# TouchPanel_ver__4.net
KiCad netlist of a schematic drawn in EAGLE
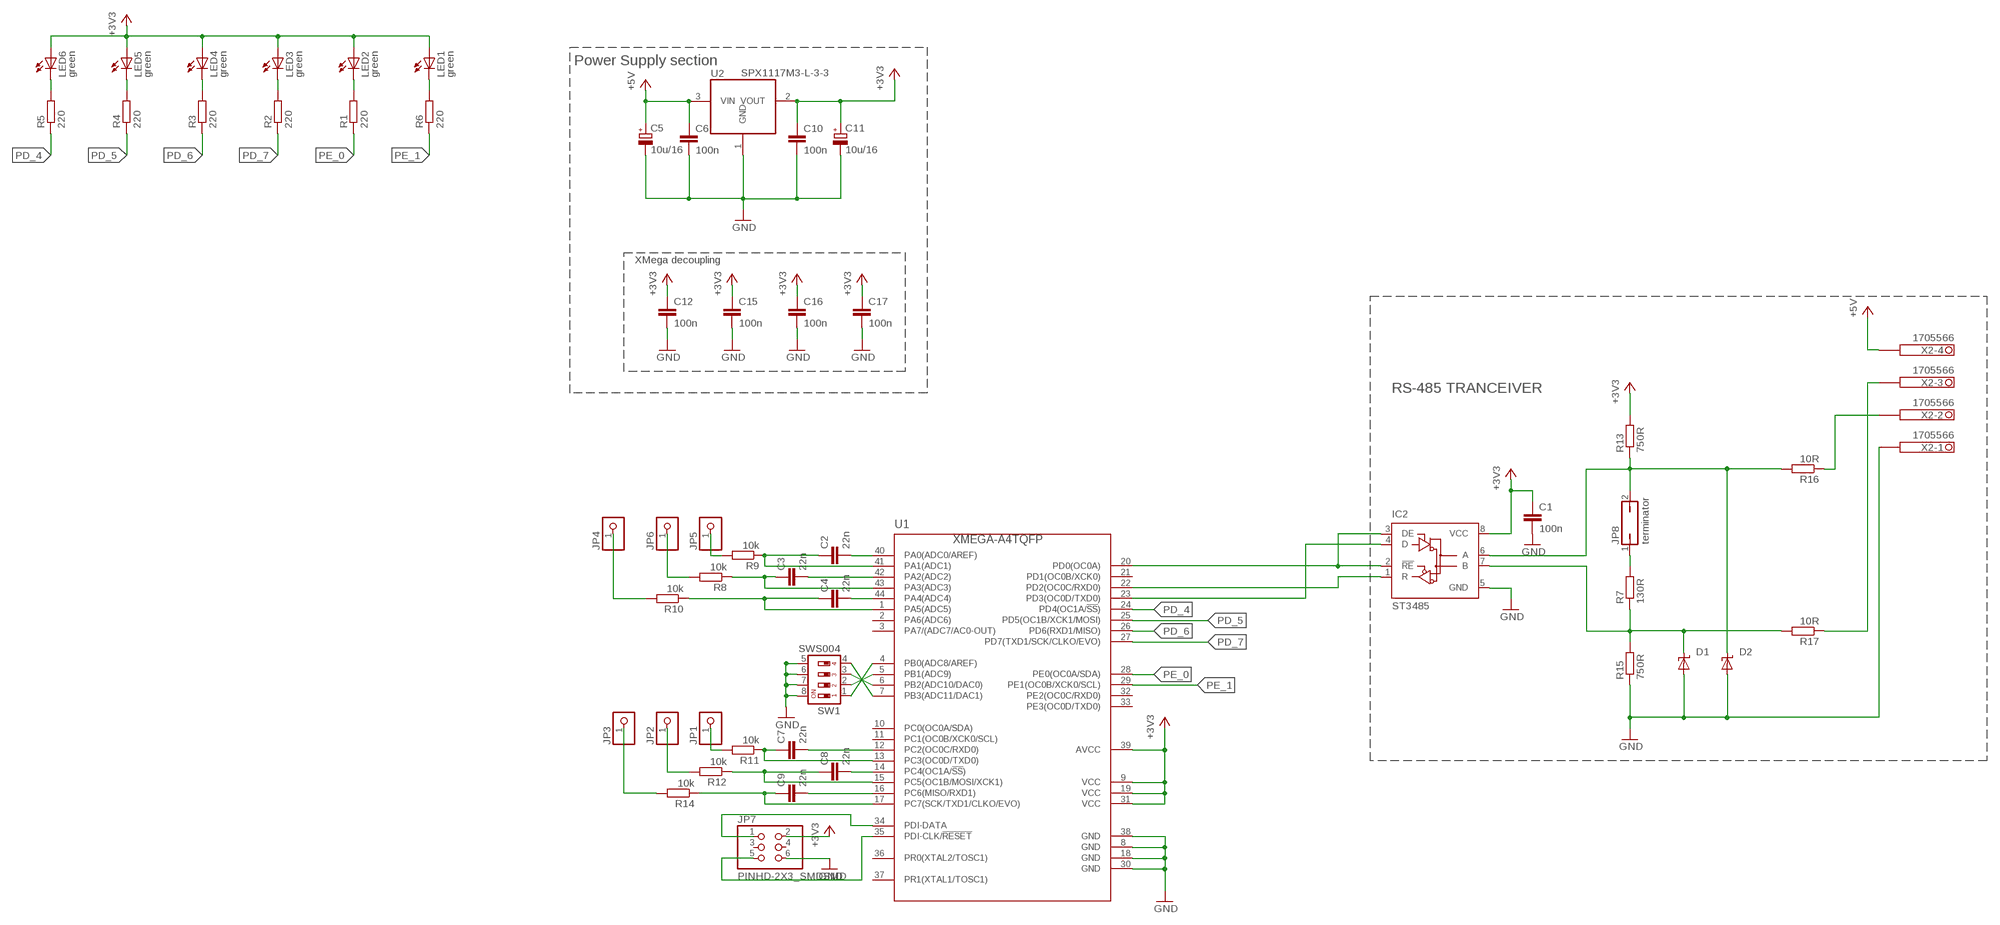
[diagram p0: schematic, sheet 1]

(export (version "E")
  (design (tool "Eeschema 10.0.6"))
  (components
    (comp (ref "C1")
      (value "100n")
      (footprint "eagle-import:C1206")
      (libsource (lib "eagle-import") (part "C-EUC1206"))
    )
    (comp (ref "C2")
      (value "22n")
      (footprint "eagle-import:C1206")
      (libsource (lib "eagle-import") (part "C-EUC1206"))
    )
    (comp (ref "C3")
      (value "22n")
      (footprint "eagle-import:C1206")
      (libsource (lib "eagle-import") (part "C-EUC1206"))
    )
    (comp (ref "C4")
      (value "22n")
      (footprint "eagle-import:C1206")
      (libsource (lib "eagle-import") (part "C-EUC1206"))
    )
    (comp (ref "C5")
      (value "10u/16")
      (footprint "eagle-import:SMC_B")
      (libsource (lib "eagle-import") (part "CPOL-EUSMCB"))
    )
    (comp (ref "C6")
      (value "100n")
      (footprint "eagle-import:C1206")
      (libsource (lib "eagle-import") (part "C-EUC1206"))
    )
    (comp (ref "C7")
      (value "22n")
      (footprint "eagle-import:C1206")
      (libsource (lib "eagle-import") (part "C-EUC1206"))
    )
    (comp (ref "C8")
      (value "22n")
      (footprint "eagle-import:C1206")
      (libsource (lib "eagle-import") (part "C-EUC1206"))
    )
    (comp (ref "C9")
      (value "22n")
      (footprint "eagle-import:C1206")
      (libsource (lib "eagle-import") (part "C-EUC1206"))
    )
    (comp (ref "C10")
      (value "100n")
      (footprint "eagle-import:C1206")
      (libsource (lib "eagle-import") (part "C-EUC1206"))
    )
    (comp (ref "C11")
      (value "10u/16")
      (footprint "eagle-import:SMC_B")
      (libsource (lib "eagle-import") (part "CPOL-EUSMCB"))
    )
    (comp (ref "C12")
      (value "100n")
      (footprint "eagle-import:C1206")
      (libsource (lib "eagle-import") (part "C-EUC1206"))
    )
    (comp (ref "C15")
      (value "100n")
      (footprint "eagle-import:C1206")
      (libsource (lib "eagle-import") (part "C-EUC1206"))
    )
    (comp (ref "C16")
      (value "100n")
      (footprint "eagle-import:C1206")
      (libsource (lib "eagle-import") (part "C-EUC1206"))
    )
    (comp (ref "C17")
      (value "100n")
      (footprint "eagle-import:C1206")
      (libsource (lib "eagle-import") (part "C-EUC1206"))
    )
    (comp (ref "D1")
      (value "SUPPRESSOR-SMBJ")
      (footprint "eagle-import:SMBJ")
      (libsource (lib "eagle-import") (part "SUPPRESSOR-SMBJ"))
    )
    (comp (ref "D2")
      (value "SUPPRESSOR-SMBJ")
      (footprint "eagle-import:SMBJ")
      (libsource (lib "eagle-import") (part "SUPPRESSOR-SMBJ"))
    )
    (comp (ref "IC2")
      (value "ST3485")
      (footprint "eagle-import:D_R-PDSO-G8")
      (libsource (lib "eagle-import") (part "75176AD"))
    )
    (comp (ref "JP1")
      (value "PINHD-1X1")
      (footprint "eagle-import:1X01")
      (libsource (lib "eagle-import") (part "PINHD-1X1"))
    )
    (comp (ref "JP2")
      (value "PINHD-1X1")
      (footprint "eagle-import:1X01")
      (libsource (lib "eagle-import") (part "PINHD-1X1"))
    )
    (comp (ref "JP3")
      (value "PINHD-1X1")
      (footprint "eagle-import:1X01")
      (libsource (lib "eagle-import") (part "PINHD-1X1"))
    )
    (comp (ref "JP4")
      (value "PINHD-1X1")
      (footprint "eagle-import:1X01")
      (libsource (lib "eagle-import") (part "PINHD-1X1"))
    )
    (comp (ref "JP5")
      (value "PINHD-1X1")
      (footprint "eagle-import:1X01")
      (libsource (lib "eagle-import") (part "PINHD-1X1"))
    )
    (comp (ref "JP6")
      (value "PINHD-1X1")
      (footprint "eagle-import:1X01")
      (libsource (lib "eagle-import") (part "PINHD-1X1"))
    )
    (comp (ref "JP7")
      (value "PINHD-2X3_SMDSMD")
      (footprint "eagle-import:2X03_SMD")
      (libsource (lib "eagle-import") (part "PINHD-2X3_SMDSMD"))
    )
    (comp (ref "JP8")
      (value "terminator")
      (footprint "eagle-import:JP1")
      (libsource (lib "eagle-import") (part "JP1Q"))
    )
    (comp (ref "LED1")
      (value "green")
      (footprint "eagle-import:MINI-TOPLED-SANTANA")
      (libsource (lib "eagle-import") (part "LEDTOPLED-SANTANA"))
    )
    (comp (ref "LED2")
      (value "green")
      (footprint "eagle-import:MINI-TOPLED-SANTANA")
      (libsource (lib "eagle-import") (part "LEDTOPLED-SANTANA"))
    )
    (comp (ref "LED3")
      (value "green")
      (footprint "eagle-import:MINI-TOPLED-SANTANA")
      (libsource (lib "eagle-import") (part "LEDTOPLED-SANTANA"))
    )
    (comp (ref "LED4")
      (value "green")
      (footprint "eagle-import:MINI-TOPLED-SANTANA")
      (libsource (lib "eagle-import") (part "LEDTOPLED-SANTANA"))
    )
    (comp (ref "LED5")
      (value "green")
      (footprint "eagle-import:MINI-TOPLED-SANTANA")
      (libsource (lib "eagle-import") (part "LEDTOPLED-SANTANA"))
    )
    (comp (ref "LED6")
      (value "green")
      (footprint "eagle-import:MINI-TOPLED-SANTANA")
      (libsource (lib "eagle-import") (part "LEDTOPLED-SANTANA"))
    )
    (comp (ref "R1")
      (value "220")
      (footprint "eagle-import:M1206")
      (libsource (lib "eagle-import") (part "R-EU_M1206"))
    )
    (comp (ref "R2")
      (value "220")
      (footprint "eagle-import:M1206")
      (libsource (lib "eagle-import") (part "R-EU_M1206"))
    )
    (comp (ref "R3")
      (value "220")
      (footprint "eagle-import:R1206")
      (libsource (lib "eagle-import") (part "R-EU_R1206"))
    )
    (comp (ref "R4")
      (value "220")
      (footprint "eagle-import:R1206")
      (libsource (lib "eagle-import") (part "R-EU_R1206"))
    )
    (comp (ref "R5")
      (value "220")
      (footprint "eagle-import:R1206")
      (libsource (lib "eagle-import") (part "R-EU_R1206"))
    )
    (comp (ref "R6")
      (value "220")
      (footprint "eagle-import:M1206")
      (libsource (lib "eagle-import") (part "R-EU_M1206"))
    )
    (comp (ref "R7")
      (value "130R")
      (footprint "eagle-import:M1206")
      (libsource (lib "eagle-import") (part "R-EU_M1206"))
    )
    (comp (ref "R8")
      (value "10k")
      (footprint "eagle-import:R1206")
      (libsource (lib "eagle-import") (part "R-EU_R1206"))
    )
    (comp (ref "R9")
      (value "10k")
      (footprint "eagle-import:R1206")
      (libsource (lib "eagle-import") (part "R-EU_R1206"))
    )
    (comp (ref "R10")
      (value "10k")
      (footprint "eagle-import:R1206")
      (libsource (lib "eagle-import") (part "R-EU_R1206"))
    )
    (comp (ref "R11")
      (value "10k")
      (footprint "eagle-import:R1206")
      (libsource (lib "eagle-import") (part "R-EU_R1206"))
    )
    (comp (ref "R12")
      (value "10k")
      (footprint "eagle-import:R1206")
      (libsource (lib "eagle-import") (part "R-EU_R1206"))
    )
    (comp (ref "R13")
      (value "750R")
      (footprint "eagle-import:M1206")
      (libsource (lib "eagle-import") (part "R-EU_M1206"))
    )
    (comp (ref "R14")
      (value "10k")
      (footprint "eagle-import:R1206")
      (libsource (lib "eagle-import") (part "R-EU_R1206"))
    )
    (comp (ref "R15")
      (value "750R")
      (footprint "eagle-import:M1206")
      (libsource (lib "eagle-import") (part "R-EU_M1206"))
    )
    (comp (ref "R16")
      (value "10R")
      (footprint "eagle-import:M1206")
      (libsource (lib "eagle-import") (part "R-EU_M1206"))
    )
    (comp (ref "R17")
      (value "10R")
      (footprint "eagle-import:M1206")
      (libsource (lib "eagle-import") (part "R-EU_M1206"))
    )
    (comp (ref "SW1")
      (value "SWS004")
      (footprint "eagle-import:SMS-004")
      (libsource (lib "eagle-import") (part "SWS004"))
    )
    (comp (ref "U1")
      (value "XMEGA-A4TQFP")
      (footprint "eagle-import:TQFP44")
      (libsource (lib "eagle-import") (part "XMEGA-A4TQFP"))
    )
    (comp (ref "U2")
      (value "SPX1117M3-L-3-3")
      (footprint "eagle-import:SOT223")
      (fields (field (name "MPN") "REG1117"))
      (libsource (lib "eagle-import") (part "REG1117"))
    )
    (comp (ref "X2")
      (value "1705566")
      (footprint "eagle-import:1705566")
      (libsource (lib "eagle-import") (part "1705566"))
    )
  )
  (nets
    (net (code "1") (name "+3V3") (class "Default")
      (node (ref "C1") (pin "1") (pinfunction "1_1") (pintype "passive"))
      (node (ref "C10") (pin "1") (pinfunction "1_1") (pintype "passive"))
      (node (ref "C11") (pin "+") (pinfunction "+_+") (pintype "passive"))
      (node (ref "C12") (pin "1") (pinfunction "1_1") (pintype "passive"))
      (node (ref "C15") (pin "1") (pinfunction "1_1") (pintype "passive"))
      (node (ref "C16") (pin "1") (pinfunction "1_1") (pintype "passive"))
      (node (ref "C17") (pin "1") (pinfunction "1_1") (pintype "passive"))
      (node (ref "IC2") (pin "8") (pinfunction "VCC_8") (pintype "power_in"))
      (node (ref "JP7") (pin "2") (pinfunction "2_2") (pintype "passive"))
      (node (ref "LED1") (pin "A") (pinfunction "A_A") (pintype "passive"))
      (node (ref "LED2") (pin "A") (pinfunction "A_A") (pintype "passive"))
      (node (ref "LED3") (pin "A") (pinfunction "A_A") (pintype "passive"))
      (node (ref "LED4") (pin "A") (pinfunction "A_A") (pintype "passive"))
      (node (ref "LED5") (pin "A") (pinfunction "A_A") (pintype "passive"))
      (node (ref "LED6") (pin "A") (pinfunction "A_A") (pintype "passive"))
      (node (ref "R13") (pin "2") (pinfunction "2_2") (pintype "passive"))
      (node (ref "U1") (pin "19") (pinfunction "VCC_19") (pintype "power_in"))
      (node (ref "U1") (pin "31") (pinfunction "VCC_31") (pintype "power_in"))
      (node (ref "U1") (pin "39") (pinfunction "AVCC_39") (pintype "power_in"))
      (node (ref "U1") (pin "9") (pinfunction "VCC_9") (pintype "power_in"))
      (node (ref "U2") (pin "2") (pinfunction "VOUT_2") (pintype "output"))
    )
    (net (code "2") (name "+5V") (class "Default")
      (node (ref "C5") (pin "+") (pinfunction "+_+") (pintype "passive"))
      (node (ref "C6") (pin "1") (pinfunction "1_1") (pintype "passive"))
      (node (ref "U2") (pin "3") (pinfunction "VIN_3") (pintype "input"))
      (node (ref "X2") (pin "4.2") (pinfunction "1B_4.2") (pintype "passive"))
    )
    (net (code "3") (name "GND") (class "Default")
      (node (ref "C1") (pin "2") (pinfunction "2_2") (pintype "passive"))
      (node (ref "C10") (pin "2") (pinfunction "2_2") (pintype "passive"))
      (node (ref "C11") (pin "-") (pinfunction "-_-") (pintype "passive"))
      (node (ref "C12") (pin "2") (pinfunction "2_2") (pintype "passive"))
      (node (ref "C15") (pin "2") (pinfunction "2_2") (pintype "passive"))
      (node (ref "C16") (pin "2") (pinfunction "2_2") (pintype "passive"))
      (node (ref "C17") (pin "2") (pinfunction "2_2") (pintype "passive"))
      (node (ref "C5") (pin "-") (pinfunction "-_-") (pintype "passive"))
      (node (ref "C6") (pin "2") (pinfunction "2_2") (pintype "passive"))
      (node (ref "D1") (pin "A") (pinfunction "A_A") (pintype "passive"))
      (node (ref "D2") (pin "A") (pinfunction "A_A") (pintype "passive"))
      (node (ref "IC2") (pin "5") (pinfunction "GND_5") (pintype "power_in"))
      (node (ref "JP7") (pin "6") (pinfunction "6_6") (pintype "passive"))
      (node (ref "R15") (pin "1") (pinfunction "1_1") (pintype "passive"))
      (node (ref "SW1") (pin "5") (pinfunction "5_5") (pintype "passive"))
      (node (ref "SW1") (pin "6") (pinfunction "6_6") (pintype "passive"))
      (node (ref "SW1") (pin "7") (pinfunction "7_7") (pintype "passive"))
      (node (ref "SW1") (pin "8") (pinfunction "8_8") (pintype "passive"))
      (node (ref "U1") (pin "18") (pinfunction "GND_18") (pintype "power_in"))
      (node (ref "U1") (pin "30") (pinfunction "GND_30") (pintype "power_in"))
      (node (ref "U1") (pin "38") (pinfunction "GND_38") (pintype "power_in"))
      (node (ref "U1") (pin "8") (pinfunction "GND_8") (pintype "power_in"))
      (node (ref "U2") (pin "1") (pinfunction "GND_1") (pintype "power_in"))
      (node (ref "X2") (pin "1.2") (pinfunction "1B_1.2") (pintype "passive"))
    )
    (net (code "4") (name "Net-(IC2-A)") (class "Default")
      (node (ref "D2") (pin "C") (pinfunction "C_C") (pintype "passive"))
      (node (ref "IC2") (pin "6") (pinfunction "A_6") (pintype "output"))
      (node (ref "JP8") (pin "2") (pinfunction "2_2") (pintype "passive"))
      (node (ref "R13") (pin "1") (pinfunction "1_1") (pintype "passive"))
      (node (ref "R16") (pin "2") (pinfunction "2_2") (pintype "passive"))
    )
    (net (code "5") (name "Net-(IC2-B)") (class "Default")
      (node (ref "D1") (pin "C") (pinfunction "C_C") (pintype "passive"))
      (node (ref "IC2") (pin "7") (pinfunction "B_7") (pintype "output"))
      (node (ref "R15") (pin "2") (pinfunction "2_2") (pintype "passive"))
      (node (ref "R17") (pin "2") (pinfunction "2_2") (pintype "passive"))
      (node (ref "R7") (pin "1") (pinfunction "1_1") (pintype "passive"))
    )
    (net (code "6") (name "Net-(IC2-D)") (class "Default")
      (node (ref "IC2") (pin "4") (pinfunction "D_4") (pintype "input"))
      (node (ref "U1") (pin "23") (pinfunction "PD3(OC0D/TXD0)_23") (pintype "bidirectional"))
    )
    (net (code "7") (name "Net-(IC2-DE)") (class "Default")
      (node (ref "IC2") (pin "2") (pinfunction "~{RE}_2") (pintype "input"))
      (node (ref "IC2") (pin "3") (pinfunction "DE_3") (pintype "input"))
      (node (ref "U1") (pin "20") (pinfunction "PD0(OC0A)_20") (pintype "bidirectional"))
    )
    (net (code "8") (name "Net-(IC2-R)") (class "Default")
      (node (ref "IC2") (pin "1") (pinfunction "R_1") (pintype "input"))
      (node (ref "U1") (pin "22") (pinfunction "PD2(OC0C/RXD0)_22") (pintype "bidirectional"))
    )
    (net (code "9") (name "Net-(JP1-Pad1)") (class "Default")
      (node (ref "JP1") (pin "1") (pinfunction "1_1") (pintype "passive"))
      (node (ref "R11") (pin "2") (pinfunction "2_2") (pintype "passive"))
    )
    (net (code "10") (name "Net-(JP2-Pad1)") (class "Default")
      (node (ref "JP2") (pin "1") (pinfunction "1_1") (pintype "passive"))
      (node (ref "R12") (pin "2") (pinfunction "2_2") (pintype "passive"))
    )
    (net (code "11") (name "Net-(JP3-Pad1)") (class "Default")
      (node (ref "JP3") (pin "1") (pinfunction "1_1") (pintype "passive"))
      (node (ref "R14") (pin "2") (pinfunction "2_2") (pintype "passive"))
    )
    (net (code "12") (name "Net-(JP4-Pad1)") (class "Default")
      (node (ref "JP4") (pin "1") (pinfunction "1_1") (pintype "passive"))
      (node (ref "R10") (pin "2") (pinfunction "2_2") (pintype "passive"))
    )
    (net (code "13") (name "Net-(JP5-Pad1)") (class "Default")
      (node (ref "JP5") (pin "1") (pinfunction "1_1") (pintype "passive"))
      (node (ref "R9") (pin "2") (pinfunction "2_2") (pintype "passive"))
    )
    (net (code "14") (name "Net-(JP6-Pad1)") (class "Default")
      (node (ref "JP6") (pin "1") (pinfunction "1_1") (pintype "passive"))
      (node (ref "R8") (pin "2") (pinfunction "2_2") (pintype "passive"))
    )
    (net (code "15") (name "Net-(JP8-Pad1)") (class "Default")
      (node (ref "JP8") (pin "1") (pinfunction "1_1") (pintype "passive"))
      (node (ref "R7") (pin "2") (pinfunction "2_2") (pintype "passive"))
    )
    (net (code "16") (name "Net-(LED1-PadC)") (class "Default")
      (node (ref "LED1") (pin "C") (pinfunction "C_C") (pintype "passive"))
      (node (ref "R6") (pin "2") (pinfunction "2_2") (pintype "passive"))
    )
    (net (code "17") (name "Net-(LED2-PadC)") (class "Default")
      (node (ref "LED2") (pin "C") (pinfunction "C_C") (pintype "passive"))
      (node (ref "R1") (pin "2") (pinfunction "2_2") (pintype "passive"))
    )
    (net (code "18") (name "Net-(LED3-PadC)") (class "Default")
      (node (ref "LED3") (pin "C") (pinfunction "C_C") (pintype "passive"))
      (node (ref "R2") (pin "2") (pinfunction "2_2") (pintype "passive"))
    )
    (net (code "19") (name "Net-(LED4-PadC)") (class "Default")
      (node (ref "LED4") (pin "C") (pinfunction "C_C") (pintype "passive"))
      (node (ref "R3") (pin "2") (pinfunction "2_2") (pintype "passive"))
    )
    (net (code "20") (name "Net-(LED5-PadC)") (class "Default")
      (node (ref "LED5") (pin "C") (pinfunction "C_C") (pintype "passive"))
      (node (ref "R4") (pin "2") (pinfunction "2_2") (pintype "passive"))
    )
    (net (code "21") (name "Net-(LED6-PadC)") (class "Default")
      (node (ref "LED6") (pin "C") (pinfunction "C_C") (pintype "passive"))
      (node (ref "R5") (pin "2") (pinfunction "2_2") (pintype "passive"))
    )
    (net (code "22") (name "Net-(U1-PA0(ADC0{slash}AREF))") (class "Default")
      (node (ref "C2") (pin "2") (pinfunction "2_2") (pintype "passive"))
      (node (ref "U1") (pin "40") (pinfunction "PA0(ADC0/AREF)_40") (pintype "bidirectional"))
    )
    (net (code "23") (name "Net-(U1-PA1(ADC1))") (class "Default")
      (node (ref "C2") (pin "1") (pinfunction "1_1") (pintype "passive"))
      (node (ref "R9") (pin "1") (pinfunction "1_1") (pintype "passive"))
      (node (ref "U1") (pin "41") (pinfunction "PA1(ADC1)_41") (pintype "bidirectional"))
    )
    (net (code "24") (name "Net-(U1-PA2(ADC2))") (class "Default")
      (node (ref "C3") (pin "2") (pinfunction "2_2") (pintype "passive"))
      (node (ref "U1") (pin "42") (pinfunction "PA2(ADC2)_42") (pintype "bidirectional"))
    )
    (net (code "25") (name "Net-(U1-PA3(ADC3))") (class "Default")
      (node (ref "C3") (pin "1") (pinfunction "1_1") (pintype "passive"))
      (node (ref "R8") (pin "1") (pinfunction "1_1") (pintype "passive"))
      (node (ref "U1") (pin "43") (pinfunction "PA3(ADC3)_43") (pintype "bidirectional"))
    )
    (net (code "26") (name "Net-(U1-PA4(ADC4))") (class "Default")
      (node (ref "C4") (pin "2") (pinfunction "2_2") (pintype "passive"))
      (node (ref "U1") (pin "44") (pinfunction "PA4(ADC4)_44") (pintype "bidirectional"))
    )
    (net (code "27") (name "Net-(U1-PA5(ADC5))") (class "Default")
      (node (ref "C4") (pin "1") (pinfunction "1_1") (pintype "passive"))
      (node (ref "R10") (pin "1") (pinfunction "1_1") (pintype "passive"))
      (node (ref "U1") (pin "1") (pinfunction "PA5(ADC5)_1") (pintype "bidirectional"))
    )
    (net (code "28") (name "Net-(U1-PB0(ADC8{slash}AREF))") (class "Default")
      (node (ref "SW1") (pin "1") (pinfunction "1_1") (pintype "passive"))
      (node (ref "U1") (pin "4") (pinfunction "PB0(ADC8/AREF)_4") (pintype "bidirectional"))
    )
    (net (code "29") (name "Net-(U1-PB1(ADC9))") (class "Default")
      (node (ref "SW1") (pin "2") (pinfunction "2_2") (pintype "passive"))
      (node (ref "U1") (pin "5") (pinfunction "PB1(ADC9)_5") (pintype "bidirectional"))
    )
    (net (code "30") (name "Net-(U1-PB2(ADC10{slash}DAC0))") (class "Default")
      (node (ref "SW1") (pin "3") (pinfunction "3_3") (pintype "passive"))
      (node (ref "U1") (pin "6") (pinfunction "PB2(ADC10/DAC0)_6") (pintype "bidirectional"))
    )
    (net (code "31") (name "Net-(U1-PB3(ADC11{slash}DAC1))") (class "Default")
      (node (ref "SW1") (pin "4") (pinfunction "4_4") (pintype "passive"))
      (node (ref "U1") (pin "7") (pinfunction "PB3(ADC11/DAC1)_7") (pintype "bidirectional"))
    )
    (net (code "32") (name "Net-(U1-PC2(OC0C{slash}RXD0))") (class "Default")
      (node (ref "C7") (pin "2") (pinfunction "2_2") (pintype "passive"))
      (node (ref "U1") (pin "12") (pinfunction "PC2(OC0C/RXD0)_12") (pintype "bidirectional"))
    )
    (net (code "33") (name "Net-(U1-PC3(OC0D{slash}TXD0))") (class "Default")
      (node (ref "C7") (pin "1") (pinfunction "1_1") (pintype "passive"))
      (node (ref "R11") (pin "1") (pinfunction "1_1") (pintype "passive"))
      (node (ref "U1") (pin "13") (pinfunction "PC3(OC0D/TXD0)_13") (pintype "bidirectional"))
    )
    (net (code "34") (name "Net-(U1-PC4(OC1A{slash}~{SS}))") (class "Default")
      (node (ref "C8") (pin "2") (pinfunction "2_2") (pintype "passive"))
      (node (ref "U1") (pin "14") (pinfunction "PC4(OC1A/~{SS})_14") (pintype "bidirectional"))
    )
    (net (code "35") (name "Net-(U1-PC5(OC1B{slash}MOSI{slash}XCK1))") (class "Default")
      (node (ref "C8") (pin "1") (pinfunction "1_1") (pintype "passive"))
      (node (ref "R12") (pin "1") (pinfunction "1_1") (pintype "passive"))
      (node (ref "U1") (pin "15") (pinfunction "PC5(OC1B/MOSI/XCK1)_15") (pintype "bidirectional"))
    )
    (net (code "36") (name "Net-(U1-PC6(MISO{slash}RXD1))") (class "Default")
      (node (ref "C9") (pin "2") (pinfunction "2_2") (pintype "passive"))
      (node (ref "U1") (pin "16") (pinfunction "PC6(MISO/RXD1)_16") (pintype "bidirectional"))
    )
    (net (code "37") (name "Net-(U1-PC7(SCK{slash}TXD1{slash}CLKO{slash}EVO))") (class "Default")
      (node (ref "C9") (pin "1") (pinfunction "1_1") (pintype "passive"))
      (node (ref "R14") (pin "1") (pinfunction "1_1") (pintype "passive"))
      (node (ref "U1") (pin "17") (pinfunction "PC7(SCK/TXD1/CLKO/EVO)_17") (pintype "bidirectional"))
    )
    (net (code "38") (name "Net-(U1-PDI-CLK{slash}~{RESET})") (class "Default")
      (node (ref "JP7") (pin "5") (pinfunction "5_5") (pintype "passive"))
      (node (ref "U1") (pin "35") (pinfunction "PDI-CLK/~{RESET}_35") (pintype "input"))
    )
    (net (code "39") (name "Net-(U1-PDI-DATA)") (class "Default")
      (node (ref "JP7") (pin "1") (pinfunction "1_1") (pintype "passive"))
      (node (ref "U1") (pin "34") (pinfunction "PDI-DATA_34") (pintype "bidirectional"))
    )
    (net (code "40") (name "Net-(X2B-1B)") (class "Default")
      (node (ref "R16") (pin "1") (pinfunction "1_1") (pintype "passive"))
      (node (ref "X2") (pin "2.2") (pinfunction "1B_2.2") (pintype "passive"))
    )
    (net (code "41") (name "Net-(X2C-1B)") (class "Default")
      (node (ref "R17") (pin "1") (pinfunction "1_1") (pintype "passive"))
      (node (ref "X2") (pin "3.2") (pinfunction "1B_3.2") (pintype "passive"))
    )
    (net (code "42") (name "PD_4") (class "Default")
      (node (ref "R5") (pin "1") (pinfunction "1_1") (pintype "passive"))
      (node (ref "U1") (pin "24") (pinfunction "PD4(OC1A/~{SS})_24") (pintype "bidirectional"))
    )
    (net (code "43") (name "PD_5") (class "Default")
      (node (ref "R4") (pin "1") (pinfunction "1_1") (pintype "passive"))
      (node (ref "U1") (pin "25") (pinfunction "PD5(OC1B/XCK1/MOSI)_25") (pintype "bidirectional"))
    )
    (net (code "44") (name "PD_6") (class "Default")
      (node (ref "R3") (pin "1") (pinfunction "1_1") (pintype "passive"))
      (node (ref "U1") (pin "26") (pinfunction "PD6(RXD1/MISO)_26") (pintype "bidirectional"))
    )
    (net (code "45") (name "PD_7") (class "Default")
      (node (ref "R2") (pin "1") (pinfunction "1_1") (pintype "passive"))
      (node (ref "U1") (pin "27") (pinfunction "PD7(TXD1/SCK/CLKO/EVO)_27") (pintype "bidirectional"))
    )
    (net (code "46") (name "PE_0") (class "Default")
      (node (ref "R1") (pin "1") (pinfunction "1_1") (pintype "passive"))
      (node (ref "U1") (pin "28") (pinfunction "PE0(OC0A/SDA)_28") (pintype "bidirectional"))
    )
    (net (code "47") (name "PE_1") (class "Default")
      (node (ref "R6") (pin "1") (pinfunction "1_1") (pintype "passive"))
      (node (ref "U1") (pin "29") (pinfunction "PE1(OC0B/XCK0/SCL)_29") (pintype "bidirectional"))
    )
    (net (code "48") (name "unconnected-(JP7-Pad3)") (class "Default")
      (node (ref "JP7") (pin "3") (pinfunction "3_3") (pintype "passive"))
    )
    (net (code "49") (name "unconnected-(JP7-Pad4)") (class "Default")
      (node (ref "JP7") (pin "4") (pinfunction "4_4") (pintype "passive"))
    )
    (net (code "50") (name "unconnected-(U1-PA6(ADC6)-Pad2)") (class "Default")
      (node (ref "U1") (pin "2") (pinfunction "PA6(ADC6)_2") (pintype "bidirectional"))
    )
    (net (code "51") (name "unconnected-(U1-PA7{slash}(ADC7{slash}AC0-OUT)-Pad3)") (class "Default")
      (node (ref "U1") (pin "3") (pinfunction "PA7/(ADC7/AC0-OUT)_3") (pintype "bidirectional"))
    )
    (net (code "52") (name "unconnected-(U1-PC0(OC0A{slash}SDA)-Pad10)") (class "Default")
      (node (ref "U1") (pin "10") (pinfunction "PC0(OC0A/SDA)_10") (pintype "bidirectional"))
    )
    (net (code "53") (name "unconnected-(U1-PC1(OC0B{slash}XCK0{slash}SCL)-Pad11)") (class "Default")
      (node (ref "U1") (pin "11") (pinfunction "PC1(OC0B/XCK0/SCL)_11") (pintype "bidirectional"))
    )
    (net (code "54") (name "unconnected-(U1-PD1(OC0B{slash}XCK0)-Pad21)") (class "Default")
      (node (ref "U1") (pin "21") (pinfunction "PD1(OC0B/XCK0)_21") (pintype "bidirectional"))
    )
    (net (code "55") (name "unconnected-(U1-PE2(OC0C{slash}RXD0)-Pad32)") (class "Default")
      (node (ref "U1") (pin "32") (pinfunction "PE2(OC0C/RXD0)_32") (pintype "bidirectional"))
    )
    (net (code "56") (name "unconnected-(U1-PE3(OC0D{slash}TXD0)-Pad33)") (class "Default")
      (node (ref "U1") (pin "33") (pinfunction "PE3(OC0D/TXD0)_33") (pintype "bidirectional"))
    )
    (net (code "57") (name "unconnected-(U1-PR0(XTAL2{slash}TOSC1)-Pad36)") (class "Default")
      (node (ref "U1") (pin "36") (pinfunction "PR0(XTAL2/TOSC1)_36") (pintype "bidirectional"))
    )
    (net (code "58") (name "unconnected-(U1-PR1(XTAL1{slash}TOSC1)-Pad37)") (class "Default")
      (node (ref "U1") (pin "37") (pinfunction "PR1(XTAL1/TOSC1)_37") (pintype "bidirectional"))
    )
    (net (code "59") (name "unconnected-(X2A-1A-Pad1.1)") (class "Default")
      (node (ref "X2") (pin "1.1") (pinfunction "1A_1.1") (pintype "passive"))
    )
    (net (code "60") (name "unconnected-(X2B-1A-Pad2.1)") (class "Default")
      (node (ref "X2") (pin "2.1") (pinfunction "1A_2.1") (pintype "passive"))
    )
    (net (code "61") (name "unconnected-(X2C-1A-Pad3.1)") (class "Default")
      (node (ref "X2") (pin "3.1") (pinfunction "1A_3.1") (pintype "passive"))
    )
    (net (code "62") (name "unconnected-(X2D-1A-Pad4.1)") (class "Default")
      (node (ref "X2") (pin "4.1") (pinfunction "1A_4.1") (pintype "passive"))
    )
  )
)
